# ESPLEDCTRL.net
KiCad netlist of a schematic drawn in EAGLE
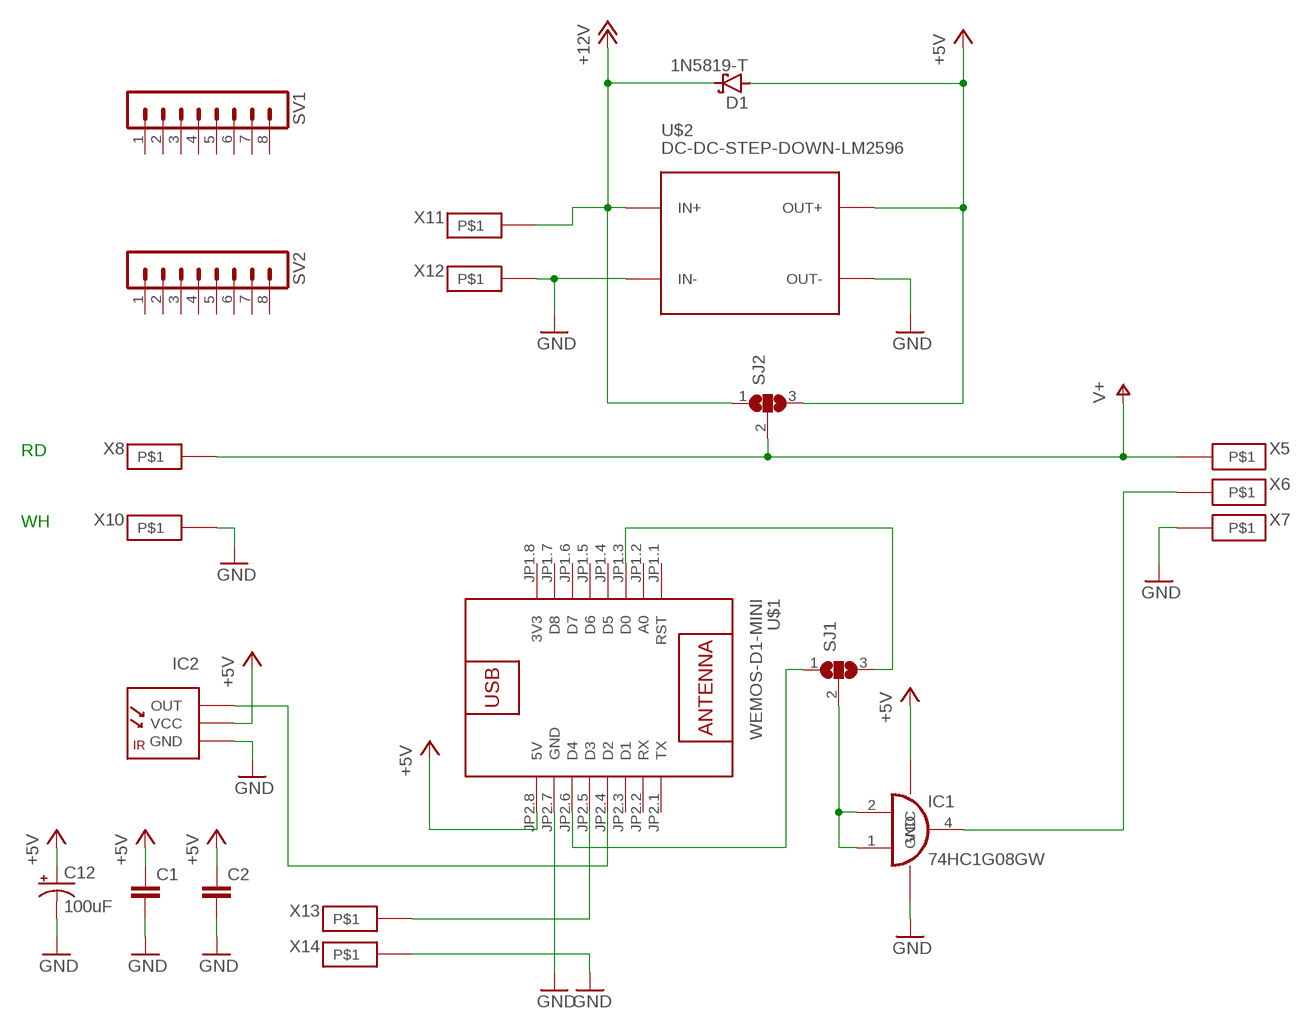
[diagram p0: schematic, sheet 1]

(export (version "E")
  (design (tool "Eeschema 10.0.6"))
  (components
    (comp (ref "C1")
      (value "C-EUC1206")
      (footprint "eagle-import:C1206")
      (libsource (lib "eagle-import") (part "C-EUC1206"))
    )
    (comp (ref "C2")
      (value "C-EUC1206")
      (footprint "eagle-import:C1206")
      (libsource (lib "eagle-import") (part "C-EUC1206"))
    )
    (comp (ref "C12")
      (value "100uF")
      (footprint "eagle-import:PANASONIC_D")
      (libsource (lib "eagle-import") (part "CPOL-USD"))
    )
    (comp (ref "D1")
      (value "1N5819-T")
      (footprint "eagle-import:DO41-7.6")
      (libsource (lib "eagle-import") (part "1N5819-T"))
    )
    (comp (ref "IC1")
      (value "74HC1G08GW")
      (footprint "eagle-import:SOT353")
      (libsource (lib "eagle-import") (part "74HC1G08GW"))
    )
    (comp (ref "IC2")
      (value "TSOP382")
      (footprint "eagle-import:TSOP38")
      (libsource (lib "eagle-import") (part "TSOP382"))
    )
    (comp (ref "SJ1")
      (value "SJ2W")
      (footprint "eagle-import:SJ_2")
      (libsource (lib "eagle-import") (part "SJ2W"))
    )
    (comp (ref "SJ2")
      (value "SJ2W")
      (footprint "eagle-import:SJ_2")
      (libsource (lib "eagle-import") (part "SJ2W"))
    )
    (comp (ref "SV1")
      (value "MA08-1")
      (footprint "eagle-import:MA08-1")
      (libsource (lib "eagle-import") (part "MA08-1"))
    )
    (comp (ref "SV2")
      (value "MA08-1")
      (footprint "eagle-import:MA08-1")
      (libsource (lib "eagle-import") (part "MA08-1"))
    )
    (comp (ref "U$1")
      (value "WEMOS-D1-MINI")
      (footprint "eagle-import:WEMOS-D1-MINI")
      (libsource (lib "eagle-import") (part "WEMOS-D1-MINI"))
    )
    (comp (ref "U$2")
      (value "DC-DC-STEP-DOWN-LM2596")
      (footprint "eagle-import:DC-DC-STEP-DOWN-LM2596")
      (libsource (lib "eagle-import") (part "DC-DC-STEP-DOWN-LM2596"))
    )
    (comp (ref "X5")
      (value "PAD2X4")
      (footprint "eagle-import:PAD2X4")
      (libsource (lib "eagle-import") (part "PAD2X4"))
    )
    (comp (ref "X6")
      (value "PAD2X4")
      (footprint "eagle-import:PAD2X4")
      (libsource (lib "eagle-import") (part "PAD2X4"))
    )
    (comp (ref "X7")
      (value "PAD2X4")
      (footprint "eagle-import:PAD2X4")
      (libsource (lib "eagle-import") (part "PAD2X4"))
    )
    (comp (ref "X8")
      (value "PAD2X4")
      (footprint "eagle-import:PAD2X4")
      (libsource (lib "eagle-import") (part "PAD2X4"))
    )
    (comp (ref "X10")
      (value "PAD2X4")
      (footprint "eagle-import:PAD2X4")
      (libsource (lib "eagle-import") (part "PAD2X4"))
    )
    (comp (ref "X11")
      (value "PAD2X4")
      (footprint "eagle-import:PAD2X4")
      (libsource (lib "eagle-import") (part "PAD2X4"))
    )
    (comp (ref "X12")
      (value "PAD2X4")
      (footprint "eagle-import:PAD2X4")
      (libsource (lib "eagle-import") (part "PAD2X4"))
    )
    (comp (ref "X13")
      (value "PAD2X4")
      (footprint "eagle-import:PAD2X4")
      (libsource (lib "eagle-import") (part "PAD2X4"))
    )
    (comp (ref "X14")
      (value "PAD2X4")
      (footprint "eagle-import:PAD2X4")
      (libsource (lib "eagle-import") (part "PAD2X4"))
    )
  )
  (nets
    (net (code "1") (name "+5V") (class "Default")
      (node (ref "C1") (pin "1") (pinfunction "1_1") (pintype "passive"))
      (node (ref "C12") (pin "+") (pinfunction "+_+") (pintype "passive"))
      (node (ref "C2") (pin "1") (pinfunction "1_1") (pintype "passive"))
      (node (ref "D1") (pin "A") (pinfunction "A_A") (pintype "passive"))
      (node (ref "IC1") (pin "5") (pinfunction "VCC_5") (pintype "power_in"))
      (node (ref "IC2") (pin "3") (pinfunction "VCC_3") (pintype "bidirectional"))
      (node (ref "SJ2") (pin "3") (pinfunction "3_3") (pintype "passive"))
      (node (ref "U$1") (pin "JP2.8") (pinfunction "5V_JP2.8") (pintype "power_in"))
      (node (ref "U$2") (pin "OUT+") (pinfunction "OUT+_OUT+") (pintype "bidirectional"))
    )
    (net (code "2") (name "+12V") (class "Default")
      (node (ref "D1") (pin "C") (pinfunction "C_C") (pintype "passive"))
      (node (ref "SJ2") (pin "1") (pinfunction "1_1") (pintype "passive"))
      (node (ref "U$2") (pin "IN+") (pinfunction "IN+_IN+") (pintype "bidirectional"))
      (node (ref "X11") (pin "P$1") (pinfunction "P$1_P$1") (pintype "bidirectional"))
    )
    (net (code "3") (name "/3V3") (class "Default")
      (node (ref "U$1") (pin "JP1.8") (pinfunction "3V3_JP1.8") (pintype "power_in"))
    )
    (net (code "4") (name "GND") (class "Default")
      (node (ref "C1") (pin "2") (pinfunction "2_2") (pintype "passive"))
      (node (ref "C12") (pin "-") (pinfunction "-_-") (pintype "passive"))
      (node (ref "C2") (pin "2") (pinfunction "2_2") (pintype "passive"))
      (node (ref "IC1") (pin "3") (pinfunction "GND_3") (pintype "power_in"))
      (node (ref "IC2") (pin "2") (pinfunction "GND_2") (pintype "bidirectional"))
      (node (ref "U$1") (pin "JP2.7") (pinfunction "GND_JP2.7") (pintype "power_in"))
      (node (ref "U$2") (pin "IN-") (pinfunction "IN-_IN-") (pintype "bidirectional"))
      (node (ref "U$2") (pin "OUT-") (pinfunction "OUT-_OUT-") (pintype "bidirectional"))
      (node (ref "X10") (pin "P$1") (pinfunction "P$1_P$1") (pintype "bidirectional"))
      (node (ref "X12") (pin "P$1") (pinfunction "P$1_P$1") (pintype "bidirectional"))
      (node (ref "X14") (pin "P$1") (pinfunction "P$1_P$1") (pintype "bidirectional"))
      (node (ref "X7") (pin "P$1") (pinfunction "P$1_P$1") (pintype "bidirectional"))
    )
    (net (code "5") (name "Net-(IC1-I0)") (class "Default")
      (node (ref "IC1") (pin "1") (pinfunction "I1_1") (pintype "input"))
      (node (ref "IC1") (pin "2") (pinfunction "I0_2") (pintype "input"))
      (node (ref "SJ1") (pin "2") (pinfunction "2_2") (pintype "passive"))
    )
    (net (code "6") (name "Net-(IC1-O)") (class "Default")
      (node (ref "IC1") (pin "4") (pinfunction "O_4") (pintype "output"))
      (node (ref "X6") (pin "P$1") (pinfunction "P$1_P$1") (pintype "bidirectional"))
    )
    (net (code "7") (name "Net-(IC2-OUT)") (class "Default")
      (node (ref "IC2") (pin "1") (pinfunction "OUT_1") (pintype "bidirectional"))
      (node (ref "U$1") (pin "JP2.4") (pinfunction "D2_JP2.4") (pintype "bidirectional"))
    )
    (net (code "8") (name "Net-(U$1-D0)") (class "Default")
      (node (ref "SJ1") (pin "3") (pinfunction "3_3") (pintype "passive"))
      (node (ref "U$1") (pin "JP1.3") (pinfunction "D0_JP1.3") (pintype "bidirectional"))
    )
    (net (code "9") (name "Net-(U$1-D3)") (class "Default")
      (node (ref "U$1") (pin "JP2.5") (pinfunction "D3_JP2.5") (pintype "bidirectional"))
      (node (ref "X13") (pin "P$1") (pinfunction "P$1_P$1") (pintype "bidirectional"))
    )
    (net (code "10") (name "Net-(U$1-D4)") (class "Default")
      (node (ref "SJ1") (pin "1") (pinfunction "1_1") (pintype "passive"))
      (node (ref "U$1") (pin "JP2.6") (pinfunction "D4_JP2.6") (pintype "bidirectional"))
    )
    (net (code "11") (name "V+") (class "Default")
      (node (ref "SJ2") (pin "2") (pinfunction "2_2") (pintype "passive"))
      (node (ref "X5") (pin "P$1") (pinfunction "P$1_P$1") (pintype "bidirectional"))
      (node (ref "X8") (pin "P$1") (pinfunction "P$1_P$1") (pintype "bidirectional"))
    )
    (net (code "12") (name "unconnected-(SV1-Pad1)") (class "Default")
      (node (ref "SV1") (pin "1") (pinfunction "1_1") (pintype "passive"))
    )
    (net (code "13") (name "unconnected-(SV1-Pad2)") (class "Default")
      (node (ref "SV1") (pin "2") (pinfunction "2_2") (pintype "passive"))
    )
    (net (code "14") (name "unconnected-(SV1-Pad3)") (class "Default")
      (node (ref "SV1") (pin "3") (pinfunction "3_3") (pintype "passive"))
    )
    (net (code "15") (name "unconnected-(SV1-Pad4)") (class "Default")
      (node (ref "SV1") (pin "4") (pinfunction "4_4") (pintype "passive"))
    )
    (net (code "16") (name "unconnected-(SV1-Pad5)") (class "Default")
      (node (ref "SV1") (pin "5") (pinfunction "5_5") (pintype "passive"))
    )
    (net (code "17") (name "unconnected-(SV1-Pad6)") (class "Default")
      (node (ref "SV1") (pin "6") (pinfunction "6_6") (pintype "passive"))
    )
    (net (code "18") (name "unconnected-(SV1-Pad7)") (class "Default")
      (node (ref "SV1") (pin "7") (pinfunction "7_7") (pintype "passive"))
    )
    (net (code "19") (name "unconnected-(SV1-Pad8)") (class "Default")
      (node (ref "SV1") (pin "8") (pinfunction "8_8") (pintype "passive"))
    )
    (net (code "20") (name "unconnected-(SV2-Pad1)") (class "Default")
      (node (ref "SV2") (pin "1") (pinfunction "1_1") (pintype "passive"))
    )
    (net (code "21") (name "unconnected-(SV2-Pad2)") (class "Default")
      (node (ref "SV2") (pin "2") (pinfunction "2_2") (pintype "passive"))
    )
    (net (code "22") (name "unconnected-(SV2-Pad3)") (class "Default")
      (node (ref "SV2") (pin "3") (pinfunction "3_3") (pintype "passive"))
    )
    (net (code "23") (name "unconnected-(SV2-Pad4)") (class "Default")
      (node (ref "SV2") (pin "4") (pinfunction "4_4") (pintype "passive"))
    )
    (net (code "24") (name "unconnected-(SV2-Pad5)") (class "Default")
      (node (ref "SV2") (pin "5") (pinfunction "5_5") (pintype "passive"))
    )
    (net (code "25") (name "unconnected-(SV2-Pad6)") (class "Default")
      (node (ref "SV2") (pin "6") (pinfunction "6_6") (pintype "passive"))
    )
    (net (code "26") (name "unconnected-(SV2-Pad7)") (class "Default")
      (node (ref "SV2") (pin "7") (pinfunction "7_7") (pintype "passive"))
    )
    (net (code "27") (name "unconnected-(SV2-Pad8)") (class "Default")
      (node (ref "SV2") (pin "8") (pinfunction "8_8") (pintype "passive"))
    )
    (net (code "28") (name "unconnected-(U$1-A0-PadJP1.2)") (class "Default")
      (node (ref "U$1") (pin "JP1.2") (pinfunction "A0_JP1.2") (pintype "bidirectional"))
    )
    (net (code "29") (name "unconnected-(U$1-D1-PadJP2.3)") (class "Default")
      (node (ref "U$1") (pin "JP2.3") (pinfunction "D1_JP2.3") (pintype "bidirectional"))
    )
    (net (code "30") (name "unconnected-(U$1-D5-PadJP1.4)") (class "Default")
      (node (ref "U$1") (pin "JP1.4") (pinfunction "D5_JP1.4") (pintype "bidirectional"))
    )
    (net (code "31") (name "unconnected-(U$1-D6-PadJP1.5)") (class "Default")
      (node (ref "U$1") (pin "JP1.5") (pinfunction "D6_JP1.5") (pintype "bidirectional"))
    )
    (net (code "32") (name "unconnected-(U$1-D7-PadJP1.6)") (class "Default")
      (node (ref "U$1") (pin "JP1.6") (pinfunction "D7_JP1.6") (pintype "bidirectional"))
    )
    (net (code "33") (name "unconnected-(U$1-D8-PadJP1.7)") (class "Default")
      (node (ref "U$1") (pin "JP1.7") (pinfunction "D8_JP1.7") (pintype "bidirectional"))
    )
    (net (code "34") (name "unconnected-(U$1-RST-PadJP1.1)") (class "Default")
      (node (ref "U$1") (pin "JP1.1") (pinfunction "RST_JP1.1") (pintype "bidirectional"))
    )
    (net (code "35") (name "unconnected-(U$1-RX-PadJP2.2)") (class "Default")
      (node (ref "U$1") (pin "JP2.2") (pinfunction "RX_JP2.2") (pintype "bidirectional"))
    )
    (net (code "36") (name "unconnected-(U$1-TX-PadJP2.1)") (class "Default")
      (node (ref "U$1") (pin "JP2.1") (pinfunction "TX_JP2.1") (pintype "bidirectional"))
    )
  )
)
